# Amplifier_PH.net
KiCad netlist of a schematic drawn in Altium Designer
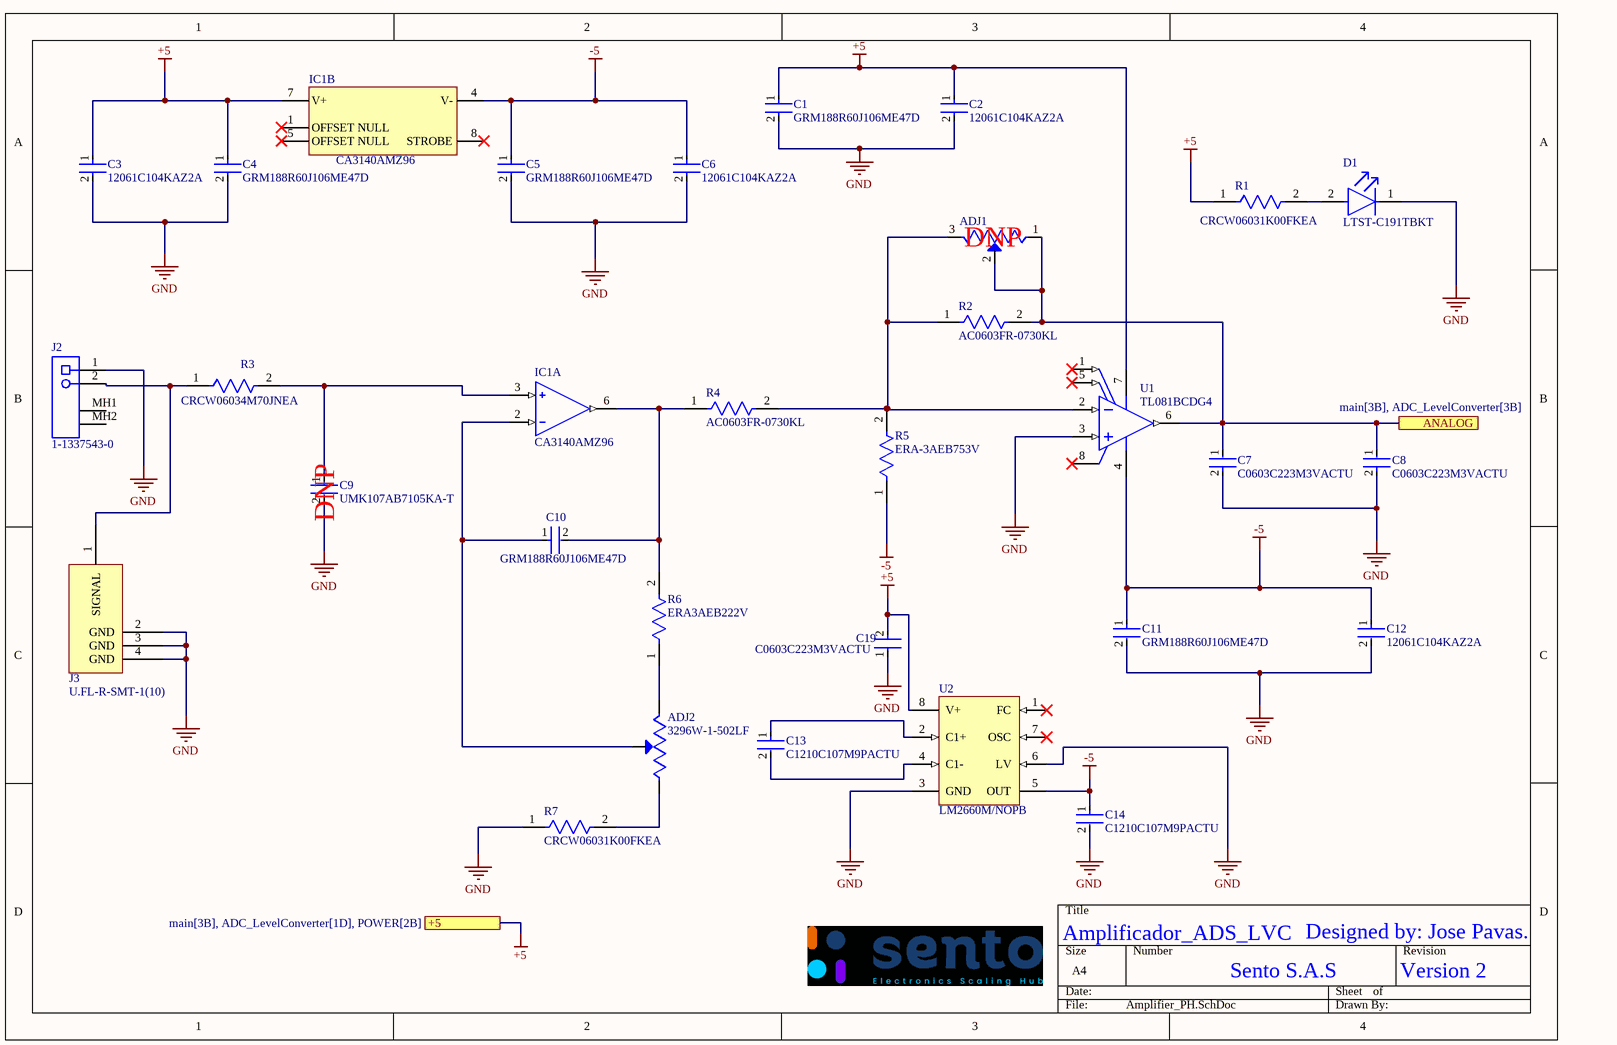
[diagram p0: Amplifier_PH.SchDoc]

(export (version "E")
  (design (tool "Eeschema 10.0.6"))
  (components
    (comp (ref "ADJ1")
      (value "~")
      (footprint "TRIM_3296W-1-502LF")
      (description "100 kOhms 0.5W, 1/2W PC Pins Through Hole Trimmer Potentiometer Cermet 25.0 Turn Top Adjustment")
      (fields (field (name "MF") "Bourns") (field (name "MP") "3296W-1-502LF"))
      (libsource (lib "3296W-1-502LF") (part "3296W-1-502LF"))
    )
    (comp (ref "ADJ2")
      (value "3296W-1-502LF")
      (footprint "TRIM_3296W-1-502LF")
      (description "5 kOhms 0.5W, 1/2W PC Pins Through Hole Trimmer Potentiometer Cermet 25.0 Turn Top Adjustment")
      (fields (field (name "MF") "Bourns") (field (name "LCSC PART NUMBER") "C60620"))
      (libsource (lib "") (part "3296W-1-502LF_1"))
    )
    (comp (ref "C1")
      (value "GRM188R60J106ME47D")
      (footprint "FP-GRM188-0_1-e0_2_0_55-IPC_A")
      (description "Chip Multilayer Ceramic Capacitors for General Purpose, 0603, 10uF, X5R, 15%, 20%, 6.3V")
      (fields (field (name "VOLTAGE") "6.3V") (field (name "TOLERANCE") "20%"))
      (libsource (lib "Altium Content Vault") (part "02cd4be3c70576c341d710602a673aa"))
    )
    (comp (ref "C2")
      (value "12061C104KAZ2A")
      (footprint "FP-1206-L_3_2_0_2-W_1_6_0-MFG")
      (description "General Purpose Ceramic Capacitor, 1206, 100nF, 10%, X7R, 15%, 100V")
      (fields (field (name "TOLERANCE") "10%") (field (name "LCSC PART NUMBER") "C726629"))
      (libsource (lib "") (part "b4654b650e69147ec39a6b967a45e02_1"))
    )
    (comp (ref "C3")
      (value "12061C104KAZ2A")
      (footprint "FP-1206-L_3_2_0_2-W_1_6_0-MFG")
      (description "General Purpose Ceramic Capacitor, 1206, 100nF, 10%, X7R, 15%, 100V")
      (fields (field (name "TOLERANCE") "10%") (field (name "LCSC PART NUMBER") "C726629"))
      (libsource (lib "") (part "b4654b650e69147ec39a6b967a45e02_1"))
    )
    (comp (ref "C4")
      (value "GRM188R60J106ME47D")
      (footprint "FP-GRM188-0_1-e0_2_0_55-IPC_A")
      (description "Chip Multilayer Ceramic Capacitors for General Purpose, 0603, 10uF, X5R, 15%, 20%, 6.3V")
      (fields (field (name "VOLTAGE") "6.3V") (field (name "TOLERANCE") "20%"))
      (libsource (lib "Altium Content Vault") (part "02cd4be3c70576c341d710602a673aa"))
    )
    (comp (ref "C5")
      (value "GRM188R60J106ME47D")
      (footprint "FP-GRM188-0_1-e0_2_0_55-IPC_A")
      (description "Chip Multilayer Ceramic Capacitors for General Purpose, 0603, 10uF, X5R, 15%, 20%, 6.3V")
      (fields (field (name "VOLTAGE") "6.3V") (field (name "TOLERANCE") "20%"))
      (libsource (lib "Altium Content Vault") (part "02cd4be3c70576c341d710602a673aa"))
    )
    (comp (ref "C6")
      (value "12061C104KAZ2A")
      (footprint "FP-1206-L_3_2_0_2-W_1_6_0-MFG")
      (description "General Purpose Ceramic Capacitor, 1206, 100nF, 10%, X7R, 15%, 100V")
      (fields (field (name "TOLERANCE") "10%") (field (name "LCSC PART NUMBER") "C726629"))
      (libsource (lib "") (part "b4654b650e69147ec39a6b967a45e02_1"))
    )
    (comp (ref "C7")
      (value "C0603C223M3VACTU")
      (footprint "FP-CGA3E-0_3-0_1-MFG")
      (description "Cap Ceramic 100nF 50V X7R 10% Pad SMD 0603 +125°C Automotive T/R")
      (fields (field (name "TOLERANCE") "10%") (field (name "VOLTAGE") "50V"))
      (libsource (lib "Altium Content Vault") (part "b4654b650e69147ec39a6b967a45e02"))
    )
    (comp (ref "C8")
      (value "C0603C223M3VACTU")
      (footprint "FP-CGA3E-0_3-0_1-MFG")
      (description "Cap Ceramic 100nF 50V X7R 10% Pad SMD 0603 +125°C Automotive T/R")
      (fields (field (name "TOLERANCE") "10%") (field (name "VOLTAGE") "50V"))
      (libsource (lib "Altium Content Vault") (part "b4654b650e69147ec39a6b967a45e02"))
    )
    (comp (ref "C9")
      (value "UMK107AB7105KA-T")
      (footprint "FP-0603-L_1_6_0_15-W_0_8-IPC_C")
      (description "Ceramic Capacitor General Use 1uF ±10% 50V X7R 0603")
      (fields (field (name "TOLERANCE") "10%") (field (name "LCSC PART NUMBER") "C15849"))
      (libsource (lib "Altium Content Vault") (part "11868f565c42a9108669ba33697ecf6"))
    )
    (comp (ref "C10")
      (value "GRM188R60J106ME47D")
      (footprint "FP-GRM188-0_1-e0_2_0_55-IPC_A")
      (description "Chip Multilayer Ceramic Capacitors for General Purpose, 0603, 10uF, X5R, 15%, 20%, 6.3V")
      (fields (field (name "VOLTAGE") "6.3V") (field (name "TOLERANCE") "20%"))
      (libsource (lib "Altium Content Vault") (part "02cd4be3c70576c341d710602a673aa"))
    )
    (comp (ref "C11")
      (value "GRM188R60J106ME47D")
      (footprint "FP-GRM188-0_1-e0_2_0_55-IPC_A")
      (description "Chip Multilayer Ceramic Capacitors for General Purpose, 0603, 10uF, X5R, 15%, 20%, 6.3V")
      (fields (field (name "VOLTAGE") "6.3V") (field (name "TOLERANCE") "20%"))
      (libsource (lib "Altium Content Vault") (part "02cd4be3c70576c341d710602a673aa"))
    )
    (comp (ref "C12")
      (value "12061C104KAZ2A")
      (footprint "FP-1206-L_3_2_0_2-W_1_6_0-MFG")
      (description "General Purpose Ceramic Capacitor, 1206, 100nF, 10%, X7R, 15%, 100V")
      (fields (field (name "TOLERANCE") "10%") (field (name "LCSC PART NUMBER") "C726629"))
      (libsource (lib "") (part "b4654b650e69147ec39a6b967a45e02_1"))
    )
    (comp (ref "C13")
      (value "C1210C107M9PACTU")
      (footprint "FP-C1210C107M9PACTU-MFG")
      (description "CAP CER 100UF 6.3V X5R 1210")
      (fields (field (name "VOLTAGE") "6.3V") (field (name "TOLERANCE") "20%"))
      (libsource (lib "") (part "b4654b650e69147ec39a6b967a45e02_1"))
    )
    (comp (ref "C14")
      (value "C1210C107M9PACTU")
      (footprint "FP-C1210C107M9PACTU-MFG")
      (description "CAP CER 100UF 6.3V X5R 1210")
      (fields (field (name "VOLTAGE") "6.3V") (field (name "TOLERANCE") "20%"))
      (libsource (lib "") (part "b4654b650e69147ec39a6b967a45e02_1"))
    )
    (comp (ref "C19")
      (value "C0603C223M3VACTU")
      (footprint "FP-CGA3E-0_3-0_1-MFG")
      (description "Cap Ceramic 100nF 50V X7R 10% Pad SMD 0603 +125°C Automotive T/R")
      (fields (field (name "TOLERANCE") "10%") (field (name "VOLTAGE") "50V"))
      (libsource (lib "Altium Content Vault") (part "b4654b650e69147ec39a6b967a45e02"))
    )
    (comp (ref "D1")
      (value "LTST-C191TBKT")
      (footprint "FP-LTST-C191TBKT-MFG")
      (description "LED BLUE CLEAR CHIP SMD")
      (fields (field (name "LCSC PART NUMBER") "C99290"))
      (libsource (lib "Altium Content Vault") (part "8706943c75ba83719d021d2fdc84c58"))
    )
    (comp (ref "IC1")
      (value "CA3140AMZ96")
      (footprint "SOIC127P600X175-8N")
      (description "CA3140AMZ96 CA3140 Series 36 V 4.5 MHz BiMOS Operational Amplifier - SOIC-8")
      (fields (field (name "LCSC PART NUMBER") "C31540"))
      (libsource (lib "Altium Content Vault") (part "CA3140AMZ96"))
    )
    (comp (ref "J2")
      (value "1-1337543-0")
      (footprint "TECO-1-1337543-0_V")
      (fields (field (name "MANUFACTURER") "TE Connectivity") (field (name "LCSC PART NUMBER") "C2837588"))
      (libsource (lib "Altium Content Vault") (part "CN-1P-F-R2_A"))
    )
    (comp (ref "J3")
      (value "U.FL-R-SMT-1(10)")
      (footprint "0734120110")
      (description "CONN UMC RCPT STR 50 OHM SMD")
      (fields
        (field (name "MANUFACTURER") "Molex, LLC")
        (field (name "MANUFACTURER PART NUMBER") "0734120110")
      )
      (libsource (lib "NodeIoT") (part "0734120110"))
    )
    (comp (ref "R1")
      (value "CRCW06031K00FKEA")
      (footprint "FP-CRCW0603-e3-MFG")
      (description "RES Thick Film, 1kΩ, 1%, 0.1W, 100ppm/°C, 0603")
      (fields (field (name "TOLERANCE") "1%") (field (name "LCSC PART NUMBER") "C22548"))
      (libsource (lib "Altium Content Vault") (part "1029c3af85768c4190bb7ad29bc67b5"))
    )
    (comp (ref "R2")
      (value "AC0603FR-0730KL")
      (footprint "FP-AC0603-IPC_C")
      (description "RES 30KΩ 1.00% 0.1W 0603")
      (fields (field (name "TOLERANCE") "1%") (field (name "LCSC PART NUMBER") "C113302"))
      (libsource (lib "Altium Content Vault") (part "1029c3af85768c4190bb7ad29bc67b5"))
    )
    (comp (ref "R3")
      (value "CRCW06034M70JNEA")
      (footprint "FP-CRCW0603-e3-MFG")
      (description "RES Thick Film, 4.7MΩ, 5%, 0.1W, 200ppm/°C, 0603")
      (fields (field (name "TOLERANCE") "5%") (field (name "LCSC PART NUMBER") "C227938"))
      (libsource (lib "Altium Content Vault") (part "1029c3af85768c4190bb7ad29bc67b5"))
    )
    (comp (ref "R4")
      (value "AC0603FR-0730KL")
      (footprint "FP-AC0603-IPC_C")
      (description "RES 30KΩ 1.00% 0.1W 0603")
      (fields (field (name "TOLERANCE") "1%") (field (name "LCSC PART NUMBER") "C113302"))
      (libsource (lib "Altium Content Vault") (part "1029c3af85768c4190bb7ad29bc67b5"))
    )
    (comp (ref "R5")
      (value "ERA-3AEB753V")
      (footprint "FP-ERA3A-MFG")
      (description "RES SMD 75K OHM 0.1% 1/10W 0603")
      (fields
        (field (name "MANUFACTURER") "Panasonic")
        (field (name "OCTOPART") "https://octopart.com/era-3aeb753v-panasonic-1225046")
      )
      (libsource (lib "Altium Content Vault") (part "1029c3af85768c4190bb7ad29bc67b5"))
    )
    (comp (ref "R6")
      (value "ERA3AEB222V")
      (footprint "FP-ERA3A-MFG")
      (description "RES SMD 2.2K OHM 0.1% 1/10W 0603")
      (fields (field (name "TOLERANCE") "0.1%") (field (name "LCSC PART NUMBER") "C858962"))
      (libsource (lib "Altium Content Vault") (part "1029c3af85768c4190bb7ad29bc67b5"))
    )
    (comp (ref "R7")
      (value "CRCW06031K00FKEA")
      (footprint "FP-CRCW0603-e3-MFG")
      (description "RES Thick Film, 1kΩ, 1%, 0.1W, 100ppm/°C, 0603")
      (fields (field (name "TOLERANCE") "1%") (field (name "LCSC PART NUMBER") "C22548"))
      (libsource (lib "Altium Content Vault") (part "1029c3af85768c4190bb7ad29bc67b5"))
    )
    (comp (ref "U1")
      (value "TL081BCDG4")
      (footprint "TI-D8_M")
      (fields (field (name "MANUFACTURER") "Texas Instruments") (field (name "LCSC PART NUMBER") "C4370484"))
      (libsource (lib "Altium Content Vault") (part "TI-AMP-S5-2-8"))
    )
    (comp (ref "U2")
      (value "LM2660M/NOPB")
      (footprint "D0008A_M")
      (description "Switched Capacitor Voltage Converter, 8-pin Narrow SOIC, Pb-Free")
      (fields (field (name "MANUFACTURER") "Texas Instruments") (field (name "LCSC PART NUMBER") "C183083"))
      (libsource (lib "Altium Content Vault") (part "PM-CHP-LM2660M-8"))
    )
  )
  (nets
    (net (code "1") (name "+5") (class "Default")
      (node (ref "C1") (pin "1") (pinfunction "1_1") (pintype "passive"))
      (node (ref "C19") (pin "2") (pinfunction "2_2") (pintype "passive"))
      (node (ref "C2") (pin "1") (pinfunction "1_1") (pintype "passive"))
      (node (ref "C3") (pin "1") (pinfunction "1_1") (pintype "passive"))
      (node (ref "C4") (pin "1") (pinfunction "1_1") (pintype "passive"))
      (node (ref "IC1") (pin "7") (pinfunction "V+_7") (pintype "passive"))
      (node (ref "R1") (pin "1") (pinfunction "1_1") (pintype "passive"))
      (node (ref "U1") (pin "7") (pinfunction "VCC+_7") (pintype "power_in"))
      (node (ref "U2") (pin "8") (pinfunction "V+_8") (pintype "power_in"))
    )
    (net (code "2") (name "-5") (class "Default")
      (node (ref "C11") (pin "1") (pinfunction "1_1") (pintype "passive"))
      (node (ref "C12") (pin "1") (pinfunction "1_1") (pintype "passive"))
      (node (ref "C14") (pin "1") (pinfunction "1_1") (pintype "passive"))
      (node (ref "C5") (pin "1") (pinfunction "1_1") (pintype "passive"))
      (node (ref "C6") (pin "1") (pinfunction "1_1") (pintype "passive"))
      (node (ref "IC1") (pin "4") (pinfunction "V-_4") (pintype "passive"))
      (node (ref "R5") (pin "1") (pinfunction "1_1") (pintype "passive"))
      (node (ref "U1") (pin "4") (pinfunction "VCC-_4") (pintype "power_in"))
      (node (ref "U2") (pin "5") (pinfunction "OUT_5") (pintype "power_in"))
    )
    (net (code "3") (name "/ANALOG") (class "Default")
      (node (ref "ADJ1") (pin "1") (pinfunction "CCW_1") (pintype "passive"))
      (node (ref "ADJ1") (pin "2") (pinfunction "WIPER_2") (pintype "passive"))
      (node (ref "C7") (pin "1") (pinfunction "1_1") (pintype "passive"))
      (node (ref "C8") (pin "1") (pinfunction "1_1") (pintype "passive"))
      (node (ref "R2") (pin "2") (pinfunction "2_2") (pintype "passive"))
      (node (ref "U1") (pin "6") (pinfunction "OUT_6") (pintype "output"))
    )
    (net (code "4") (name "GND") (class "Default")
      (node (ref "C1") (pin "2") (pinfunction "2_2") (pintype "passive"))
      (node (ref "C11") (pin "2") (pinfunction "2_2") (pintype "passive"))
      (node (ref "C12") (pin "2") (pinfunction "2_2") (pintype "passive"))
      (node (ref "C14") (pin "2") (pinfunction "2_2") (pintype "passive"))
      (node (ref "C19") (pin "1") (pinfunction "1_1") (pintype "passive"))
      (node (ref "C2") (pin "2") (pinfunction "2_2") (pintype "passive"))
      (node (ref "C3") (pin "2") (pinfunction "2_2") (pintype "passive"))
      (node (ref "C4") (pin "2") (pinfunction "2_2") (pintype "passive"))
      (node (ref "C5") (pin "2") (pinfunction "2_2") (pintype "passive"))
      (node (ref "C6") (pin "2") (pinfunction "2_2") (pintype "passive"))
      (node (ref "C7") (pin "2") (pinfunction "2_2") (pintype "passive"))
      (node (ref "C8") (pin "2") (pinfunction "2_2") (pintype "passive"))
      (node (ref "C9") (pin "2") (pinfunction "2_2") (pintype "passive"))
      (node (ref "D1") (pin "1") (pinfunction "C_1") (pintype "passive"))
      (node (ref "J2") (pin "1") (pinfunction "1_1") (pintype "passive"))
      (node (ref "J3") (pin "2") (pinfunction "GND_2") (pintype "passive"))
      (node (ref "J3") (pin "3") (pinfunction "GND_3") (pintype "passive"))
      (node (ref "J3") (pin "4") (pinfunction "GND_4") (pintype "passive"))
      (node (ref "R7") (pin "1") (pinfunction "1_1") (pintype "passive"))
      (node (ref "U1") (pin "3") (pinfunction "IN+_3") (pintype "input"))
      (node (ref "U2") (pin "3") (pinfunction "GND_3") (pintype "power_in"))
      (node (ref "U2") (pin "6") (pinfunction "LV_6") (pintype "input"))
    )
    (net (code "5") (name "Net-(ADJ1-CW)") (class "Default")
      (node (ref "ADJ1") (pin "3") (pinfunction "CW_3") (pintype "passive"))
      (node (ref "R2") (pin "1") (pinfunction "1_1") (pintype "passive"))
      (node (ref "R4") (pin "2") (pinfunction "2_2") (pintype "passive"))
      (node (ref "R5") (pin "2") (pinfunction "2_2") (pintype "passive"))
      (node (ref "U1") (pin "2") (pinfunction "IN-_2") (pintype "input"))
    )
    (net (code "6") (name "Net-(ADJ2-CCW)") (class "Default")
      (node (ref "ADJ2") (pin "1") (pinfunction "CCW_1") (pintype "passive"))
      (node (ref "R7") (pin "2") (pinfunction "2_2") (pintype "passive"))
    )
    (net (code "7") (name "Net-(ADJ2-CW)") (class "Default")
      (node (ref "ADJ2") (pin "3") (pinfunction "CW_3") (pintype "passive"))
      (node (ref "R6") (pin "1") (pinfunction "1_1") (pintype "passive"))
    )
    (net (code "8") (name "Net-(ADJ2-WIPER)") (class "Default")
      (node (ref "ADJ2") (pin "2") (pinfunction "WIPER_2") (pintype "passive"))
      (node (ref "C10") (pin "1") (pinfunction "1_1") (pintype "passive"))
      (node (ref "IC1") (pin "2") (pinfunction "INV_INPUT_2") (pintype "input"))
    )
    (net (code "9") (name "Net-(D1-A)") (class "Default")
      (node (ref "D1") (pin "2") (pinfunction "A_2") (pintype "passive"))
      (node (ref "R1") (pin "2") (pinfunction "2_2") (pintype "passive"))
    )
    (net (code "10") (name "Net-(IC1A-NON-INV_INPUT)") (class "Default")
      (node (ref "C9") (pin "1") (pinfunction "1_1") (pintype "passive"))
      (node (ref "IC1") (pin "3") (pinfunction "NON-INV_INPUT_3") (pintype "input"))
      (node (ref "R3") (pin "2") (pinfunction "2_2") (pintype "passive"))
    )
    (net (code "11") (name "Net-(IC1A-OUTPUT)") (class "Default")
      (node (ref "C10") (pin "2") (pinfunction "2_2") (pintype "passive"))
      (node (ref "IC1") (pin "6") (pinfunction "OUTPUT_6") (pintype "output"))
      (node (ref "R4") (pin "1") (pinfunction "1_1") (pintype "passive"))
      (node (ref "R6") (pin "2") (pinfunction "2_2") (pintype "passive"))
    )
    (net (code "12") (name "Net-(J3-SIGNAL)") (class "Default")
      (node (ref "J2") (pin "2") (pinfunction "2_2") (pintype "passive"))
      (node (ref "J3") (pin "1") (pinfunction "SIGNAL_1") (pintype "passive"))
      (node (ref "R3") (pin "1") (pinfunction "1_1") (pintype "passive"))
    )
    (net (code "13") (name "Net-(U2-C1+)") (class "Default")
      (node (ref "C13") (pin "1") (pinfunction "1_1") (pintype "passive"))
      (node (ref "U2") (pin "2") (pinfunction "C1+_2") (pintype "input"))
    )
    (net (code "14") (name "Net-(U2-C1-)") (class "Default")
      (node (ref "C13") (pin "2") (pinfunction "2_2") (pintype "passive"))
      (node (ref "U2") (pin "4") (pinfunction "C1-_4") (pintype "input"))
    )
    (net (code "15") (name "unconnected-(IC1B-OFFSET_NULL-Pad1)") (class "Default")
      (node (ref "IC1") (pin "1") (pinfunction "OFFSET_NULL_1") (pintype "passive+no_connect"))
    )
    (net (code "16") (name "unconnected-(IC1B-OFFSET_NULL-Pad5)") (class "Default")
      (node (ref "IC1") (pin "5") (pinfunction "OFFSET_NULL_5") (pintype "passive+no_connect"))
    )
    (net (code "17") (name "unconnected-(IC1B-STROBE-Pad8)") (class "Default")
      (node (ref "IC1") (pin "8") (pinfunction "STROBE_8") (pintype "passive+no_connect"))
    )
    (net (code "18") (name "unconnected-(J2-PadMH1)") (class "Default")
      (node (ref "J2") (pin "MH1") (pinfunction "MH1_MH1") (pintype "passive"))
    )
    (net (code "19") (name "unconnected-(J2-PadMH2)") (class "Default")
      (node (ref "J2") (pin "MH2") (pinfunction "MH2_MH2") (pintype "passive"))
    )
    (net (code "20") (name "unconnected-(U1-NC-Pad8)") (class "Default")
      (node (ref "U1") (pin "8") (pinfunction "NC_8") (pintype "passive+no_connect"))
    )
    (net (code "21") (name "unconnected-(U1-OFFSET_N1-Pad1)") (class "Default")
      (node (ref "U1") (pin "1") (pinfunction "OFFSET_N1_1") (pintype "input+no_connect"))
    )
    (net (code "22") (name "unconnected-(U1-OFFSET_N2-Pad5)") (class "Default")
      (node (ref "U1") (pin "5") (pinfunction "OFFSET_N2_5") (pintype "input+no_connect"))
    )
    (net (code "23") (name "unconnected-(U2-FC-Pad1)") (class "Default")
      (node (ref "U2") (pin "1") (pinfunction "FC_1") (pintype "input+no_connect"))
    )
    (net (code "24") (name "unconnected-(U2-OSC-Pad7)") (class "Default")
      (node (ref "U2") (pin "7") (pinfunction "OSC_7") (pintype "input+no_connect"))
    )
  )
)
